# ECG_AFE_ADS1292_test.net
KiCad netlist of a schematic drawn in Altium Designer
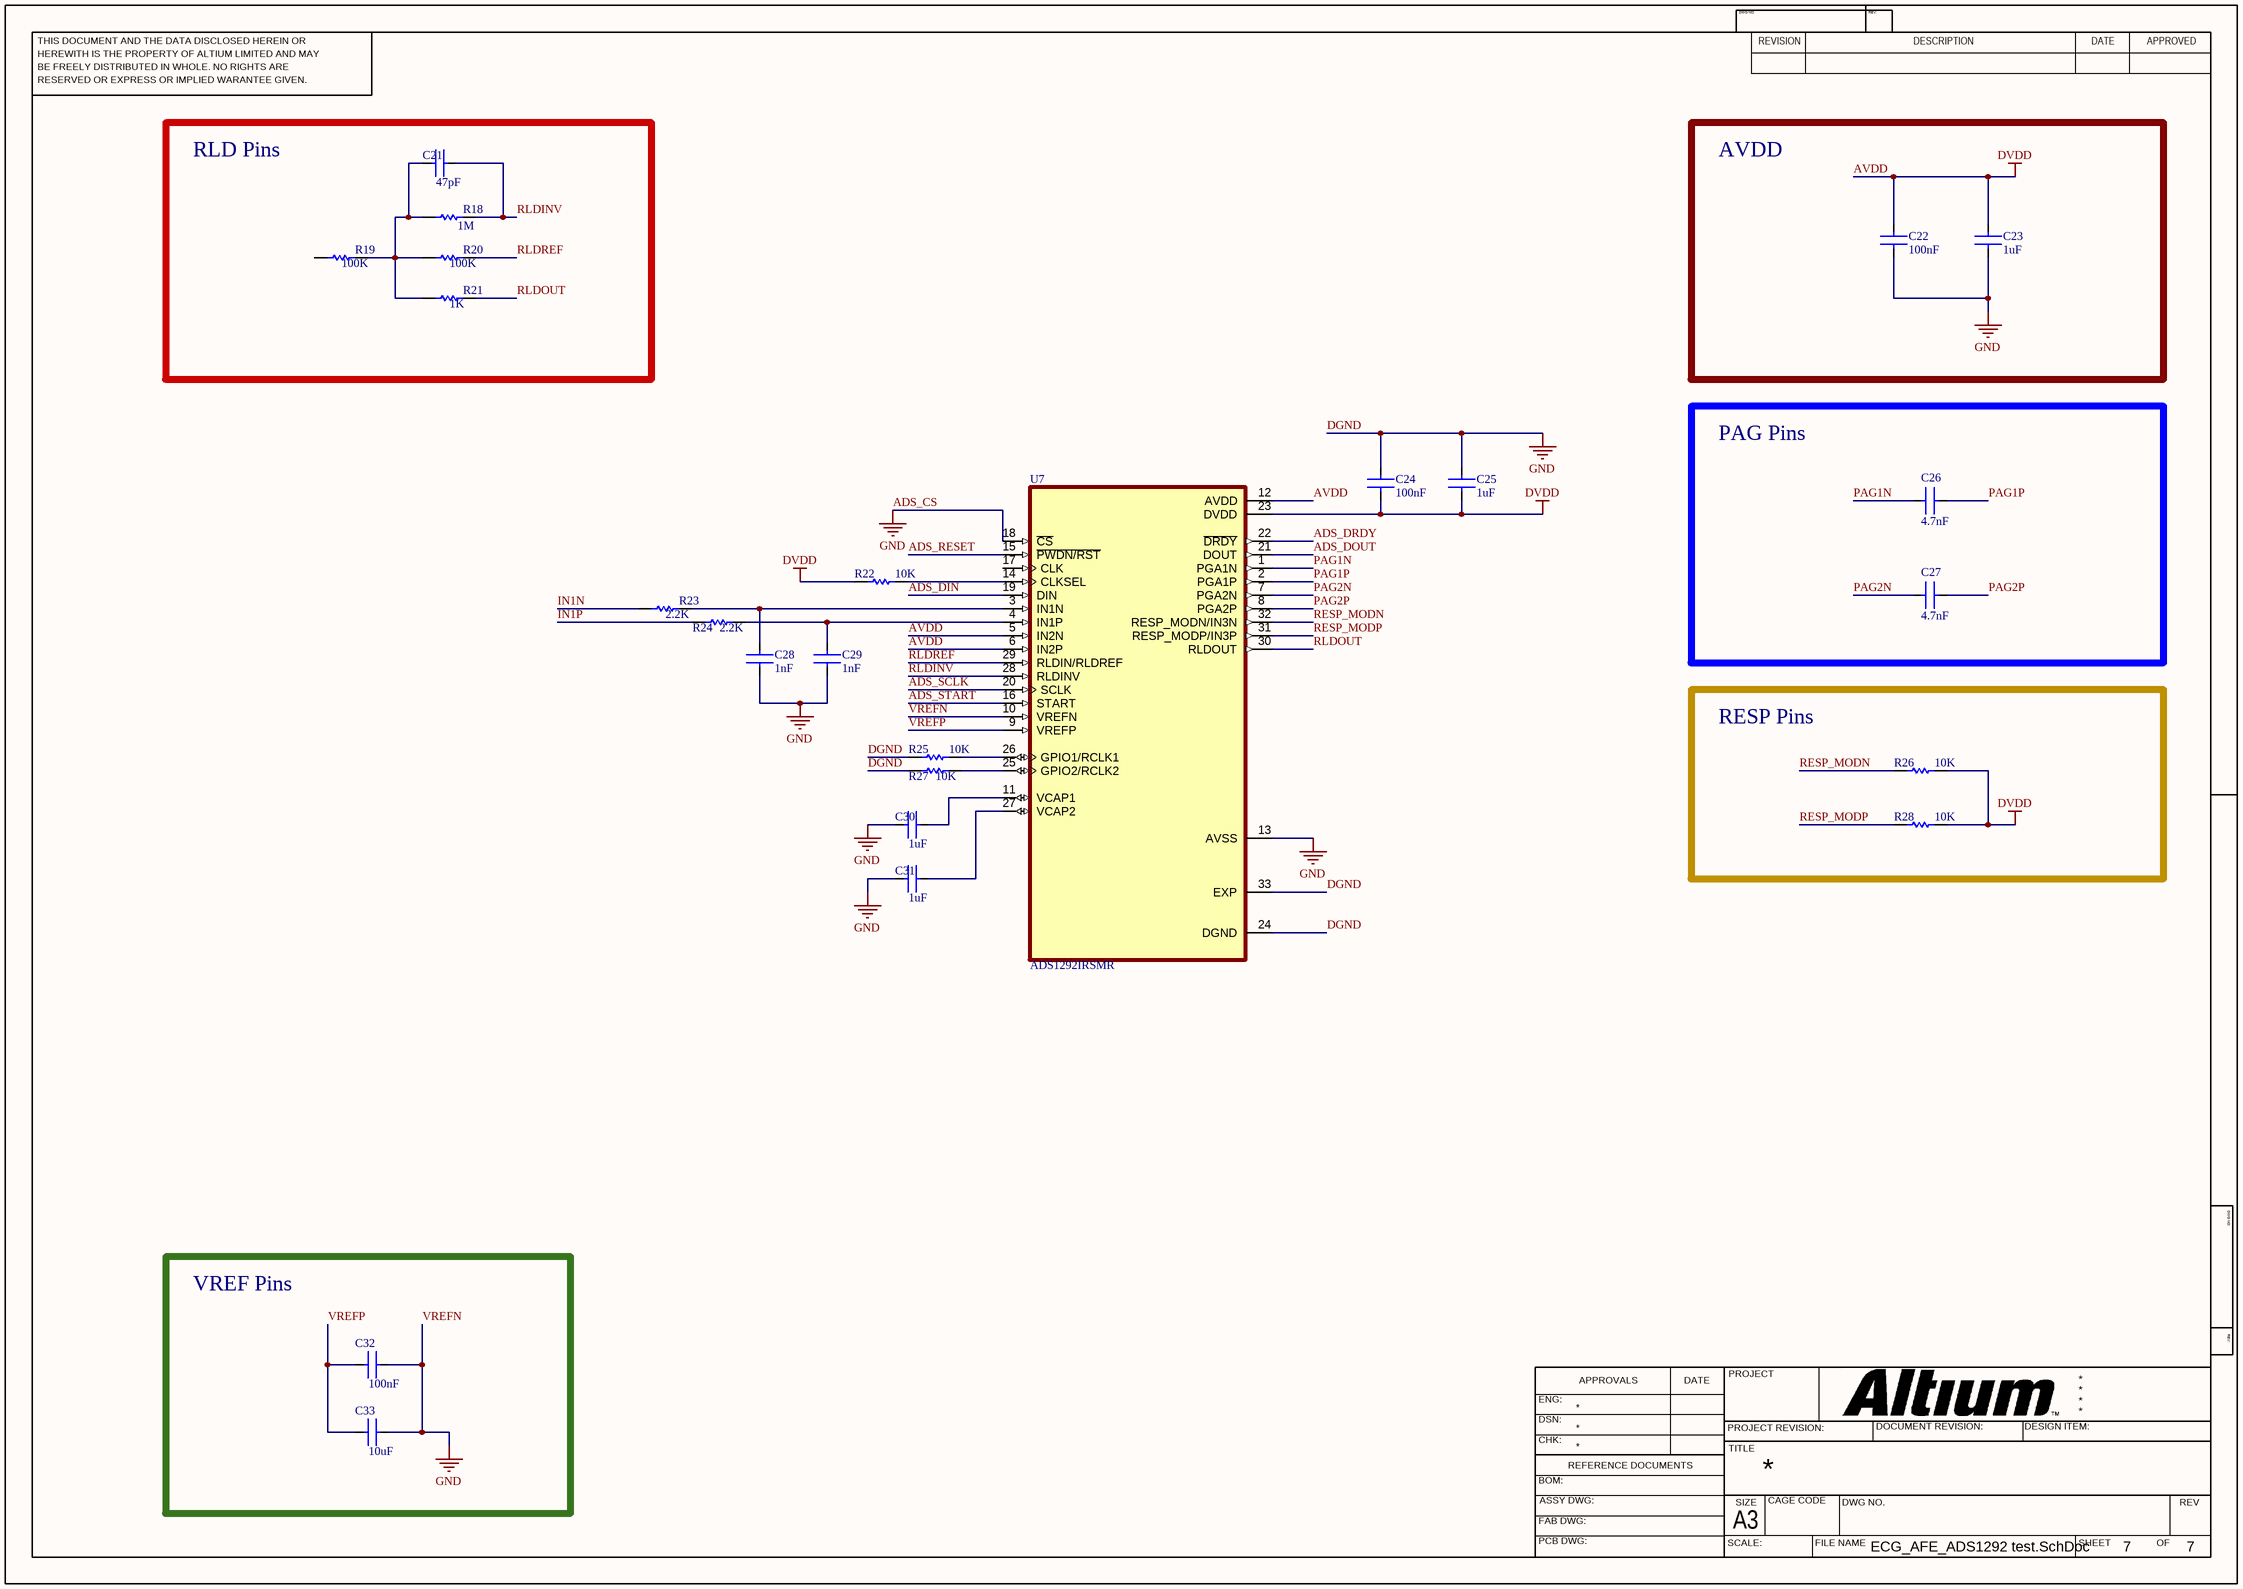
[diagram p0: ECG_AFE_ADS1292 test.SchDoc]

(export (version "E")
  (design (tool "Eeschema 10.0.6"))
  (components
    (comp (ref "C21")
      (value "47pF")
      (footprint "C_0805")
      (libsource (lib "ecg_device_components") (part "CAP-0805-16V-SMD-IPC_A"))
    )
    (comp (ref "C22")
      (value "100nF")
      (footprint "C_0805")
      (libsource (lib "ecg_device_components") (part "CAP-0805-16V-SMD-IPC_A"))
    )
    (comp (ref "C23")
      (value "1uF")
      (footprint "C_0805")
      (libsource (lib "ecg_device_components") (part "CAP-0805-16V-SMD-IPC_A"))
    )
    (comp (ref "C24")
      (value "100nF")
      (footprint "C_0805")
      (libsource (lib "ecg_device_components") (part "CAP-0805-16V-SMD-IPC_A"))
    )
    (comp (ref "C25")
      (value "1uF")
      (footprint "C_0805")
      (libsource (lib "ecg_device_components") (part "CAP-0805-16V-SMD-IPC_A"))
    )
    (comp (ref "C26")
      (value "4.7nF")
      (footprint "C_0805")
      (libsource (lib "ecg_device_components") (part "CAP-0805-16V-SMD-IPC_A"))
    )
    (comp (ref "C27")
      (value "4.7nF")
      (footprint "C_0805")
      (libsource (lib "ecg_device_components") (part "CAP-0805-16V-SMD-IPC_A"))
    )
    (comp (ref "C28")
      (value "1nF")
      (footprint "C_0805")
      (libsource (lib "ecg_device_components") (part "CAP-0805-16V-SMD-IPC_A"))
    )
    (comp (ref "C29")
      (value "1nF")
      (footprint "C_0805")
      (libsource (lib "ecg_device_components") (part "CAP-0805-16V-SMD-IPC_A"))
    )
    (comp (ref "C30")
      (value "1uF")
      (footprint "C_0805")
      (libsource (lib "ecg_device_components") (part "CAP-0805-16V-SMD-IPC_A"))
    )
    (comp (ref "C31")
      (value "1uF")
      (footprint "C_0805")
      (libsource (lib "ecg_device_components") (part "CAP-0805-16V-SMD-IPC_A"))
    )
    (comp (ref "C32")
      (value "100nF")
      (footprint "C_0805")
      (libsource (lib "ecg_device_components") (part "CAP-0805-16V-SMD-IPC_A"))
    )
    (comp (ref "C33")
      (value "10uF")
      (footprint "C_0805")
      (libsource (lib "ecg_device_components") (part "CAP-0805-16V-SMD-IPC_A"))
    )
    (comp (ref "R18")
      (value "1M")
      (footprint "RESC2013X60X35ML10T20")
      (libsource (lib "ecg_device_components") (part "10k 0805"))
    )
    (comp (ref "R19")
      (value "100K")
      (footprint "RESC2013X60X35ML10T20")
      (libsource (lib "ecg_device_components") (part "10k 0805"))
    )
    (comp (ref "R20")
      (value "100K")
      (footprint "RESC2013X60X35ML10T20")
      (libsource (lib "ecg_device_components") (part "10k 0805"))
    )
    (comp (ref "R21")
      (value "1K")
      (footprint "RESC2013X60X35ML10T20")
      (libsource (lib "ecg_device_components") (part "10k 0805"))
    )
    (comp (ref "R22")
      (value "10K")
      (footprint "RESC2013X60X35ML10T20")
      (libsource (lib "ecg_device_components") (part "10k 0805"))
    )
    (comp (ref "R23")
      (value "2.2K")
      (footprint "RESC2013X60X35ML10T20")
      (libsource (lib "ecg_device_components") (part "10k 0805"))
    )
    (comp (ref "R24")
      (value "2.2K")
      (footprint "RESC2013X60X35ML10T20")
      (libsource (lib "ecg_device_components") (part "10k 0805"))
    )
    (comp (ref "R25")
      (value "10K")
      (footprint "RESC2013X60X35ML10T20")
      (libsource (lib "ecg_device_components") (part "10k 0805"))
    )
    (comp (ref "R26")
      (value "10K")
      (footprint "RESC2013X60X35ML10T20")
      (libsource (lib "ecg_device_components") (part "10k 0805"))
    )
    (comp (ref "R27")
      (value "10K")
      (footprint "RESC2013X60X35ML10T20")
      (libsource (lib "ecg_device_components") (part "10k 0805"))
    )
    (comp (ref "R28")
      (value "10K")
      (footprint "RESC2013X60X35ML10T20")
      (libsource (lib "ecg_device_components") (part "10k 0805"))
    )
    (comp (ref "U7")
      (value "ADS1292IRSMR")
      (footprint "QFN40P400X400X100-33N")
      (description "24-bit, 2-ch, Low-Power Analog Front END (AFE) for ECG Applications")
      (fields (field (name "MF") "Texas Instruments"))
      (libsource (lib "ecg_device_components") (part "ADS1292IRSMR"))
    )
  )
  (nets
    (net (code "1") (name "/ADS_DIN") (class "Default")
      (node (ref "U7") (pin "19") (pinfunction "DIN_19") (pintype "input"))
    )
    (net (code "2") (name "/ADS_DOUT") (class "Default")
      (node (ref "U7") (pin "21") (pinfunction "DOUT_21") (pintype "output"))
    )
    (net (code "3") (name "/ADS_DRDY") (class "Default")
      (node (ref "U7") (pin "22") (pinfunction "~{DRDY}_22") (pintype "output"))
    )
    (net (code "4") (name "/ADS_RESET") (class "Default")
      (node (ref "U7") (pin "15") (pinfunction "~{PWDN/RST}_15") (pintype "input"))
    )
    (net (code "5") (name "/ADS_SCLK") (class "Default")
      (node (ref "U7") (pin "20") (pinfunction "SCLK_20") (pintype "input"))
    )
    (net (code "6") (name "/ADS_START") (class "Default")
      (node (ref "U7") (pin "16") (pinfunction "START_16") (pintype "input"))
    )
    (net (code "7") (name "/IN1N") (class "Default")
      (node (ref "R23") (pin "1") (pinfunction "1_1") (pintype "passive"))
    )
    (net (code "8") (name "/IN1P") (class "Default")
      (node (ref "R24") (pin "1") (pinfunction "1_1") (pintype "passive"))
    )
    (net (code "9") (name "/PAG1N") (class "Default")
      (node (ref "C26") (pin "2") (pinfunction "2_2") (pintype "passive"))
      (node (ref "U7") (pin "1") (pinfunction "PGA1N_1") (pintype "output"))
    )
    (net (code "10") (name "/PAG1P") (class "Default")
      (node (ref "C26") (pin "1") (pinfunction "1_1") (pintype "passive"))
      (node (ref "U7") (pin "2") (pinfunction "PGA1P_2") (pintype "output"))
    )
    (net (code "11") (name "/PAG2N") (class "Default")
      (node (ref "C27") (pin "2") (pinfunction "2_2") (pintype "passive"))
      (node (ref "U7") (pin "7") (pinfunction "PGA2N_7") (pintype "output"))
    )
    (net (code "12") (name "/PAG2P") (class "Default")
      (node (ref "C27") (pin "1") (pinfunction "1_1") (pintype "passive"))
      (node (ref "U7") (pin "8") (pinfunction "PGA2P_8") (pintype "output"))
    )
    (net (code "13") (name "/RESP_MODN") (class "Default")
      (node (ref "R26") (pin "1") (pinfunction "1_1") (pintype "passive"))
      (node (ref "U7") (pin "32") (pinfunction "RESP_MODN/IN3N_32") (pintype "output"))
    )
    (net (code "14") (name "/RESP_MODP") (class "Default")
      (node (ref "R28") (pin "1") (pinfunction "1_1") (pintype "passive"))
      (node (ref "U7") (pin "31") (pinfunction "RESP_MODP/IN3P_31") (pintype "output"))
    )
    (net (code "15") (name "/RLDINV") (class "Default")
      (node (ref "C21") (pin "2") (pinfunction "2_2") (pintype "passive"))
      (node (ref "R18") (pin "2") (pinfunction "2_2") (pintype "passive"))
      (node (ref "U7") (pin "28") (pinfunction "RLDINV_28") (pintype "input"))
    )
    (net (code "16") (name "/RLDOUT") (class "Default")
      (node (ref "R21") (pin "2") (pinfunction "2_2") (pintype "passive"))
      (node (ref "U7") (pin "30") (pinfunction "RLDOUT_30") (pintype "output"))
    )
    (net (code "17") (name "/RLDREF") (class "Default")
      (node (ref "R20") (pin "2") (pinfunction "2_2") (pintype "passive"))
      (node (ref "U7") (pin "29") (pinfunction "RLDIN/RLDREF_29") (pintype "input"))
    )
    (net (code "18") (name "/VREFP") (class "Default")
      (node (ref "C32") (pin "1") (pinfunction "1_1") (pintype "passive"))
      (node (ref "C33") (pin "1") (pinfunction "1_1") (pintype "passive"))
      (node (ref "U7") (pin "9") (pinfunction "VREFP_9") (pintype "input"))
    )
    (net (code "19") (name "DVDD") (class "Default")
      (node (ref "C22") (pin "2") (pinfunction "2_2") (pintype "passive"))
      (node (ref "C23") (pin "2") (pinfunction "2_2") (pintype "passive"))
      (node (ref "C24") (pin "1") (pinfunction "1_1") (pintype "passive"))
      (node (ref "C25") (pin "1") (pinfunction "1_1") (pintype "passive"))
      (node (ref "R22") (pin "1") (pinfunction "1_1") (pintype "passive"))
      (node (ref "R26") (pin "2") (pinfunction "2_2") (pintype "passive"))
      (node (ref "R28") (pin "2") (pinfunction "2_2") (pintype "passive"))
      (node (ref "U7") (pin "12") (pinfunction "AVDD_12") (pintype "power_in"))
      (node (ref "U7") (pin "23") (pinfunction "DVDD_23") (pintype "power_in"))
      (node (ref "U7") (pin "5") (pinfunction "IN2N_5") (pintype "input"))
      (node (ref "U7") (pin "6") (pinfunction "IN2P_6") (pintype "input"))
    )
    (net (code "20") (name "GND") (class "Default")
      (node (ref "C22") (pin "1") (pinfunction "1_1") (pintype "passive"))
      (node (ref "C23") (pin "1") (pinfunction "1_1") (pintype "passive"))
      (node (ref "C24") (pin "2") (pinfunction "2_2") (pintype "passive"))
      (node (ref "C25") (pin "2") (pinfunction "2_2") (pintype "passive"))
      (node (ref "C28") (pin "1") (pinfunction "1_1") (pintype "passive"))
      (node (ref "C29") (pin "1") (pinfunction "1_1") (pintype "passive"))
      (node (ref "C30") (pin "1") (pinfunction "1_1") (pintype "passive"))
      (node (ref "C31") (pin "1") (pinfunction "1_1") (pintype "passive"))
      (node (ref "C32") (pin "2") (pinfunction "2_2") (pintype "passive"))
      (node (ref "C33") (pin "2") (pinfunction "2_2") (pintype "passive"))
      (node (ref "R25") (pin "1") (pinfunction "1_1") (pintype "passive"))
      (node (ref "R27") (pin "1") (pinfunction "1_1") (pintype "passive"))
      (node (ref "U7") (pin "10") (pinfunction "VREFN_10") (pintype "input"))
      (node (ref "U7") (pin "13") (pinfunction "AVSS_13") (pintype "power_in"))
      (node (ref "U7") (pin "18") (pinfunction "~{CS}_18") (pintype "input"))
      (node (ref "U7") (pin "24") (pinfunction "DGND_24") (pintype "power_in"))
      (node (ref "U7") (pin "33") (pinfunction "EXP_33") (pintype "power_in"))
    )
    (net (code "21") (name "Net-(C21-Pad1)") (class "Default")
      (node (ref "C21") (pin "1") (pinfunction "1_1") (pintype "passive"))
      (node (ref "R18") (pin "1") (pinfunction "1_1") (pintype "passive"))
      (node (ref "R19") (pin "2") (pinfunction "2_2") (pintype "passive"))
      (node (ref "R20") (pin "1") (pinfunction "1_1") (pintype "passive"))
      (node (ref "R21") (pin "1") (pinfunction "1_1") (pintype "passive"))
    )
    (net (code "22") (name "Net-(U7-CLKSEL)") (class "Default")
      (node (ref "R22") (pin "2") (pinfunction "2_2") (pintype "passive"))
      (node (ref "U7") (pin "14") (pinfunction "CLKSEL_14") (pintype "input"))
    )
    (net (code "23") (name "Net-(U7-GPIO1{slash}RCLK1)") (class "Default")
      (node (ref "R25") (pin "2") (pinfunction "2_2") (pintype "passive"))
      (node (ref "U7") (pin "26") (pinfunction "GPIO1/RCLK1_26") (pintype "bidirectional"))
    )
    (net (code "24") (name "Net-(U7-GPIO2{slash}RCLK2)") (class "Default")
      (node (ref "R27") (pin "2") (pinfunction "2_2") (pintype "passive"))
      (node (ref "U7") (pin "25") (pinfunction "GPIO2/RCLK2_25") (pintype "bidirectional"))
    )
    (net (code "25") (name "Net-(U7-IN1N)") (class "Default")
      (node (ref "C28") (pin "2") (pinfunction "2_2") (pintype "passive"))
      (node (ref "R23") (pin "2") (pinfunction "2_2") (pintype "passive"))
      (node (ref "U7") (pin "3") (pinfunction "IN1N_3") (pintype "input"))
    )
    (net (code "26") (name "Net-(U7-IN1P)") (class "Default")
      (node (ref "C29") (pin "2") (pinfunction "2_2") (pintype "passive"))
      (node (ref "R24") (pin "2") (pinfunction "2_2") (pintype "passive"))
      (node (ref "U7") (pin "4") (pinfunction "IN1P_4") (pintype "input"))
    )
    (net (code "27") (name "Net-(U7-VCAP1)") (class "Default")
      (node (ref "C30") (pin "2") (pinfunction "2_2") (pintype "passive"))
      (node (ref "U7") (pin "11") (pinfunction "VCAP1_11") (pintype "bidirectional"))
    )
    (net (code "28") (name "Net-(U7-VCAP2)") (class "Default")
      (node (ref "C31") (pin "2") (pinfunction "2_2") (pintype "passive"))
      (node (ref "U7") (pin "27") (pinfunction "VCAP2_27") (pintype "bidirectional"))
    )
    (net (code "29") (name "unconnected-(R19-Pad1)") (class "Default")
      (node (ref "R19") (pin "1") (pinfunction "1_1") (pintype "passive"))
    )
    (net (code "30") (name "unconnected-(U7-CLK-Pad17)") (class "Default")
      (node (ref "U7") (pin "17") (pinfunction "CLK_17") (pintype "input"))
    )
  )
)
